# ch37x-cart.net
KiCad netlist of a schematic drawn in EAGLE
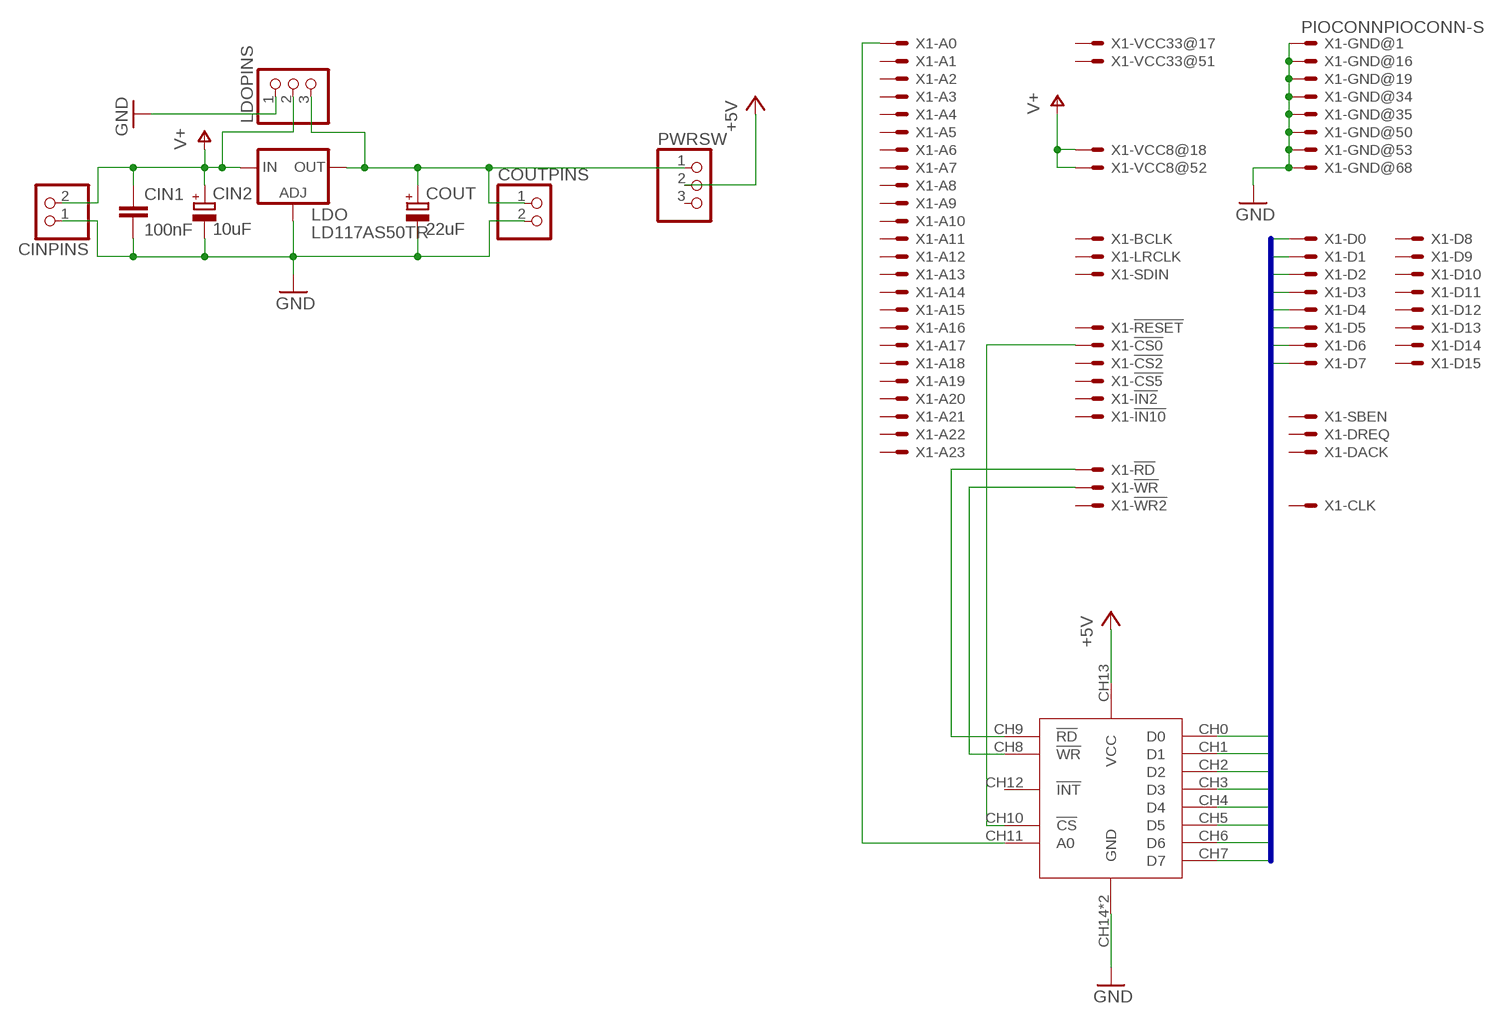
[diagram p0: schematic, sheet 1]

(export (version "E")
  (design (tool "Eeschema 10.0.6"))
  (components
    (comp (ref "CH37XBOARD")
      (value "CH375B-BOARD")
      (footprint "eagle-import:CH375B-BOARD")
      (libsource (lib "eagle-import") (part "CH375B-BOARD"))
    )
    (comp (ref "CIN1")
      (value "100nF")
      (footprint "eagle-import:C0603K")
      (libsource (lib "eagle-import") (part "C-EUC0603K"))
    )
    (comp (ref "CIN2")
      (value "10uF")
      (footprint "eagle-import:A_3216-18W")
      (libsource (lib "eagle-import") (part "CPOL-EUA/3216-18W"))
    )
    (comp (ref "CINPINS")
      (value "PINHD-1X2")
      (footprint "eagle-import:1X02")
      (libsource (lib "eagle-import") (part "PINHD-1X2"))
    )
    (comp (ref "COUT")
      (value "22uF")
      (footprint "eagle-import:A_3216-18W")
      (libsource (lib "eagle-import") (part "CPOL-EUA/3216-18W"))
    )
    (comp (ref "COUTPINS")
      (value "PINHD-1X2")
      (footprint "eagle-import:1X02")
      (libsource (lib "eagle-import") (part "PINHD-1X2"))
    )
    (comp (ref "LDO")
      (value "LD117AS50TR")
      (footprint "eagle-import:SOT223")
      (libsource (lib "eagle-import") (part "LD117A?S50TR"))
    )
    (comp (ref "LDOPINS")
      (value "PINHD-1X3")
      (footprint "eagle-import:1X03")
      (libsource (lib "eagle-import") (part "PINHD-1X3"))
    )
    (comp (ref "PWRSW")
      (value "PINHD-1X3")
      (footprint "eagle-import:1X03")
      (libsource (lib "eagle-import") (part "PINHD-1X3"))
    )
    (comp (ref "X1")
      (value "PIOCONNPIOCONN-S")
      (footprint "eagle-import:PIOCONN")
      (libsource (lib "eagle-import") (part "PIOCONNPIOCONN-S"))
    )
  )
  (nets
    (net (code "1") (name "+5V") (class "Default")
      (node (ref "CH37XBOARD") (pin "CH13") (pinfunction "VCC_CH13") (pintype "bidirectional"))
      (node (ref "PWRSW") (pin "2") (pinfunction "2_2") (pintype "passive"))
    )
    (net (code "2") (name "/D0") (class "Default")
      (node (ref "CH37XBOARD") (pin "CH0") (pinfunction "D0_CH0") (pintype "bidirectional"))
      (node (ref "X1") (pin "6") (pinfunction "S_6") (pintype "passive"))
    )
    (net (code "3") (name "/D1") (class "Default")
      (node (ref "CH37XBOARD") (pin "CH1") (pinfunction "D1_CH1") (pintype "bidirectional"))
      (node (ref "X1") (pin "40") (pinfunction "S_40") (pintype "passive"))
    )
    (net (code "4") (name "/D2") (class "Default")
      (node (ref "CH37XBOARD") (pin "CH2") (pinfunction "D2_CH2") (pintype "bidirectional"))
      (node (ref "X1") (pin "7") (pinfunction "S_7") (pintype "passive"))
    )
    (net (code "5") (name "/D3") (class "Default")
      (node (ref "CH37XBOARD") (pin "CH3") (pinfunction "D3_CH3") (pintype "bidirectional"))
      (node (ref "X1") (pin "41") (pinfunction "S_41") (pintype "passive"))
    )
    (net (code "6") (name "/D4") (class "Default")
      (node (ref "CH37XBOARD") (pin "CH4") (pinfunction "D4_CH4") (pintype "bidirectional"))
      (node (ref "X1") (pin "8") (pinfunction "S_8") (pintype "passive"))
    )
    (net (code "7") (name "/D5") (class "Default")
      (node (ref "CH37XBOARD") (pin "CH5") (pinfunction "D5_CH5") (pintype "bidirectional"))
      (node (ref "X1") (pin "42") (pinfunction "S_42") (pintype "passive"))
    )
    (net (code "8") (name "/D6") (class "Default")
      (node (ref "CH37XBOARD") (pin "CH6") (pinfunction "D6_CH6") (pintype "bidirectional"))
      (node (ref "X1") (pin "9") (pinfunction "S_9") (pintype "passive"))
    )
    (net (code "9") (name "/D7") (class "Default")
      (node (ref "CH37XBOARD") (pin "CH7") (pinfunction "D7_CH7") (pintype "bidirectional"))
      (node (ref "X1") (pin "43") (pinfunction "S_43") (pintype "passive"))
    )
    (net (code "10") (name "GND") (class "Default")
      (node (ref "CH37XBOARD") (pin "CH14") (pinfunction "GND_CH14") (pintype "bidirectional"))
      (node (ref "CH37XBOARD") (pin "CH15") (pinfunction "GND_CH15") (pintype "bidirectional"))
      (node (ref "CIN1") (pin "2") (pinfunction "2_2") (pintype "passive"))
      (node (ref "CIN2") (pin "-") (pinfunction "-_-") (pintype "passive"))
      (node (ref "CINPINS") (pin "1") (pinfunction "1_1") (pintype "passive"))
      (node (ref "COUT") (pin "-") (pinfunction "-_-") (pintype "passive"))
      (node (ref "COUTPINS") (pin "2") (pinfunction "2_2") (pintype "passive"))
      (node (ref "LDO") (pin "1") (pinfunction "ADJ_1") (pintype "input"))
      (node (ref "LDOPINS") (pin "1") (pinfunction "1_1") (pintype "passive"))
      (node (ref "X1") (pin "1") (pinfunction "S_1") (pintype "passive"))
      (node (ref "X1") (pin "16") (pinfunction "S_16") (pintype "passive"))
      (node (ref "X1") (pin "19") (pinfunction "S_19") (pintype "passive"))
      (node (ref "X1") (pin "34") (pinfunction "S_34") (pintype "passive"))
      (node (ref "X1") (pin "35") (pinfunction "S_35") (pintype "passive"))
      (node (ref "X1") (pin "50") (pinfunction "S_50") (pintype "passive"))
      (node (ref "X1") (pin "53") (pinfunction "S_53") (pintype "passive"))
      (node (ref "X1") (pin "68") (pinfunction "S_68") (pintype "passive"))
    )
    (net (code "11") (name "Net-(CH37XBOARD-A0)") (class "Default")
      (node (ref "CH37XBOARD") (pin "CH11") (pinfunction "A0_CH11") (pintype "bidirectional"))
      (node (ref "X1") (pin "14") (pinfunction "S_14") (pintype "passive"))
    )
    (net (code "12") (name "Net-(CH37XBOARD-~{CS})") (class "Default")
      (node (ref "CH37XBOARD") (pin "CH10") (pinfunction "~{CS}_CH10") (pintype "bidirectional"))
      (node (ref "X1") (pin "4") (pinfunction "S_4") (pintype "passive"))
    )
    (net (code "13") (name "Net-(CH37XBOARD-~{RD})") (class "Default")
      (node (ref "CH37XBOARD") (pin "CH9") (pinfunction "~{RD}_CH9") (pintype "bidirectional"))
      (node (ref "X1") (pin "30") (pinfunction "S_30") (pintype "passive"))
    )
    (net (code "14") (name "Net-(CH37XBOARD-~{WR})") (class "Default")
      (node (ref "CH37XBOARD") (pin "CH8") (pinfunction "~{WR}_CH8") (pintype "bidirectional"))
      (node (ref "X1") (pin "64") (pinfunction "S_64") (pintype "passive"))
    )
    (net (code "15") (name "Net-(LDO-OUT)") (class "Default")
      (node (ref "COUT") (pin "+") (pinfunction "+_+") (pintype "passive"))
      (node (ref "COUTPINS") (pin "1") (pinfunction "1_1") (pintype "passive"))
      (node (ref "LDO") (pin "4") (pinfunction "OUT_4") (pintype "passive"))
      (node (ref "LDOPINS") (pin "3") (pinfunction "3_3") (pintype "passive"))
      (node (ref "PWRSW") (pin "1") (pinfunction "1_1") (pintype "passive"))
    )
    (net (code "16") (name "V+") (class "Default")
      (node (ref "CIN1") (pin "1") (pinfunction "1_1") (pintype "passive"))
      (node (ref "CIN2") (pin "+") (pinfunction "+_+") (pintype "passive"))
      (node (ref "CINPINS") (pin "2") (pinfunction "2_2") (pintype "passive"))
      (node (ref "LDO") (pin "3") (pinfunction "IN_3") (pintype "input"))
      (node (ref "LDOPINS") (pin "2") (pinfunction "2_2") (pintype "passive"))
      (node (ref "X1") (pin "18") (pinfunction "S_18") (pintype "passive"))
      (node (ref "X1") (pin "52") (pinfunction "S_52") (pintype "passive"))
    )
    (net (code "17") (name "unconnected-(CH37XBOARD-~{INT}-PadCH12)") (class "Default")
      (node (ref "CH37XBOARD") (pin "CH12") (pinfunction "~{INT}_CH12") (pintype "bidirectional"))
    )
    (net (code "18") (name "unconnected-(PWRSW-Pad3)") (class "Default")
      (node (ref "PWRSW") (pin "3") (pinfunction "3_3") (pintype "passive"))
    )
    (net (code "19") (name "unconnected-(X1AA-S-Pad49)") (class "Default")
      (node (ref "X1") (pin "49") (pinfunction "S_49") (pintype "passive"))
    )
    (net (code "20") (name "unconnected-(X1AB-S-Pad20)") (class "Default")
      (node (ref "X1") (pin "20") (pinfunction "S_20") (pintype "passive"))
    )
    (net (code "21") (name "unconnected-(X1AC-S-Pad54)") (class "Default")
      (node (ref "X1") (pin "54") (pinfunction "S_54") (pintype "passive"))
    )
    (net (code "22") (name "unconnected-(X1AD-S-Pad21)") (class "Default")
      (node (ref "X1") (pin "21") (pinfunction "S_21") (pintype "passive"))
    )
    (net (code "23") (name "unconnected-(X1AE-S-Pad55)") (class "Default")
      (node (ref "X1") (pin "55") (pinfunction "S_55") (pintype "passive"))
    )
    (net (code "24") (name "unconnected-(X1AF-S-Pad22)") (class "Default")
      (node (ref "X1") (pin "22") (pinfunction "S_22") (pintype "passive"))
    )
    (net (code "25") (name "unconnected-(X1AG-S-Pad56)") (class "Default")
      (node (ref "X1") (pin "56") (pinfunction "S_56") (pintype "passive"))
    )
    (net (code "26") (name "unconnected-(X1AH-S-Pad33)") (class "Default")
      (node (ref "X1") (pin "33") (pinfunction "S_33") (pintype "passive"))
    )
    (net (code "27") (name "unconnected-(X1AI-S-Pad32)") (class "Default")
      (node (ref "X1") (pin "32") (pinfunction "S_32") (pintype "passive"))
    )
    (net (code "28") (name "unconnected-(X1AL-S-Pad11)") (class "Default")
      (node (ref "X1") (pin "11") (pinfunction "S_11") (pintype "passive"))
    )
    (net (code "29") (name "unconnected-(X1AM-S-Pad45)") (class "Default")
      (node (ref "X1") (pin "45") (pinfunction "S_45") (pintype "passive"))
    )
    (net (code "30") (name "unconnected-(X1AN-S-Pad12)") (class "Default")
      (node (ref "X1") (pin "12") (pinfunction "S_12") (pintype "passive"))
    )
    (net (code "31") (name "unconnected-(X1AO-S-Pad46)") (class "Default")
      (node (ref "X1") (pin "46") (pinfunction "S_46") (pintype "passive"))
    )
    (net (code "32") (name "unconnected-(X1AP-S-Pad13)") (class "Default")
      (node (ref "X1") (pin "13") (pinfunction "S_13") (pintype "passive"))
    )
    (net (code "33") (name "unconnected-(X1AQ-S-Pad47)") (class "Default")
      (node (ref "X1") (pin "47") (pinfunction "S_47") (pintype "passive"))
    )
    (net (code "34") (name "unconnected-(X1AX-S-Pad10)") (class "Default")
      (node (ref "X1") (pin "10") (pinfunction "S_10") (pintype "passive"))
    )
    (net (code "35") (name "unconnected-(X1AY-S-Pad44)") (class "Default")
      (node (ref "X1") (pin "44") (pinfunction "S_44") (pintype "passive"))
    )
    (net (code "36") (name "unconnected-(X1AZ-S-Pad36)") (class "Default")
      (node (ref "X1") (pin "36") (pinfunction "S_36") (pintype "passive"))
    )
    (net (code "37") (name "unconnected-(X1B-S-Pad39)") (class "Default")
      (node (ref "X1") (pin "39") (pinfunction "S_39") (pintype "passive"))
    )
    (net (code "38") (name "unconnected-(X1BA-S-Pad3)") (class "Default")
      (node (ref "X1") (pin "3") (pinfunction "S_3") (pintype "passive"))
    )
    (net (code "39") (name "unconnected-(X1BJ-S-Pad66)") (class "Default")
      (node (ref "X1") (pin "66") (pinfunction "S_66") (pintype "passive"))
    )
    (net (code "40") (name "unconnected-(X1BK-S-Pad5)") (class "Default")
      (node (ref "X1") (pin "5") (pinfunction "S_5") (pintype "passive"))
    )
    (net (code "41") (name "unconnected-(X1BL-S-Pad67)") (class "Default")
      (node (ref "X1") (pin "67") (pinfunction "S_67") (pintype "passive"))
    )
    (net (code "42") (name "unconnected-(X1BM-S-Pad17)") (class "Default")
      (node (ref "X1") (pin "17") (pinfunction "S_17") (pintype "passive"))
    )
    (net (code "43") (name "unconnected-(X1BN-S-Pad51)") (class "Default")
      (node (ref "X1") (pin "51") (pinfunction "S_51") (pintype "passive"))
    )
    (net (code "44") (name "unconnected-(X1C-S-Pad65)") (class "Default")
      (node (ref "X1") (pin "65") (pinfunction "S_65") (pintype "passive"))
    )
    (net (code "45") (name "unconnected-(X1D-S-Pad37)") (class "Default")
      (node (ref "X1") (pin "37") (pinfunction "S_37") (pintype "passive"))
    )
    (net (code "46") (name "unconnected-(X1E-S-Pad31)") (class "Default")
      (node (ref "X1") (pin "31") (pinfunction "S_31") (pintype "passive"))
    )
    (net (code "47") (name "unconnected-(X1G-S-Pad2)") (class "Default")
      (node (ref "X1") (pin "2") (pinfunction "S_2") (pintype "passive"))
    )
    (net (code "48") (name "unconnected-(X1I-S-Pad38)") (class "Default")
      (node (ref "X1") (pin "38") (pinfunction "S_38") (pintype "passive"))
    )
    (net (code "49") (name "unconnected-(X1K-S-Pad48)") (class "Default")
      (node (ref "X1") (pin "48") (pinfunction "S_48") (pintype "passive"))
    )
    (net (code "50") (name "unconnected-(X1L-S-Pad23)") (class "Default")
      (node (ref "X1") (pin "23") (pinfunction "S_23") (pintype "passive"))
    )
    (net (code "51") (name "unconnected-(X1M-S-Pad57)") (class "Default")
      (node (ref "X1") (pin "57") (pinfunction "S_57") (pintype "passive"))
    )
    (net (code "52") (name "unconnected-(X1N-S-Pad24)") (class "Default")
      (node (ref "X1") (pin "24") (pinfunction "S_24") (pintype "passive"))
    )
    (net (code "53") (name "unconnected-(X1O-S-Pad58)") (class "Default")
      (node (ref "X1") (pin "58") (pinfunction "S_58") (pintype "passive"))
    )
    (net (code "54") (name "unconnected-(X1P-S-Pad25)") (class "Default")
      (node (ref "X1") (pin "25") (pinfunction "S_25") (pintype "passive"))
    )
    (net (code "55") (name "unconnected-(X1Q-S-Pad59)") (class "Default")
      (node (ref "X1") (pin "59") (pinfunction "S_59") (pintype "passive"))
    )
    (net (code "56") (name "unconnected-(X1R-S-Pad26)") (class "Default")
      (node (ref "X1") (pin "26") (pinfunction "S_26") (pintype "passive"))
    )
    (net (code "57") (name "unconnected-(X1S-S-Pad60)") (class "Default")
      (node (ref "X1") (pin "60") (pinfunction "S_60") (pintype "passive"))
    )
    (net (code "58") (name "unconnected-(X1T-S-Pad27)") (class "Default")
      (node (ref "X1") (pin "27") (pinfunction "S_27") (pintype "passive"))
    )
    (net (code "59") (name "unconnected-(X1U-S-Pad61)") (class "Default")
      (node (ref "X1") (pin "61") (pinfunction "S_61") (pintype "passive"))
    )
    (net (code "60") (name "unconnected-(X1V-S-Pad15)") (class "Default")
      (node (ref "X1") (pin "15") (pinfunction "S_15") (pintype "passive"))
    )
    (net (code "61") (name "unconnected-(X1W-S-Pad28)") (class "Default")
      (node (ref "X1") (pin "28") (pinfunction "S_28") (pintype "passive"))
    )
    (net (code "62") (name "unconnected-(X1X-S-Pad62)") (class "Default")
      (node (ref "X1") (pin "62") (pinfunction "S_62") (pintype "passive"))
    )
    (net (code "63") (name "unconnected-(X1Y-S-Pad29)") (class "Default")
      (node (ref "X1") (pin "29") (pinfunction "S_29") (pintype "passive"))
    )
    (net (code "64") (name "unconnected-(X1Z-S-Pad63)") (class "Default")
      (node (ref "X1") (pin "63") (pinfunction "S_63") (pintype "passive"))
    )
  )
)
